# STM32F103xx_LQFP48.net
KiCad netlist of a schematic drawn in Altium Designer
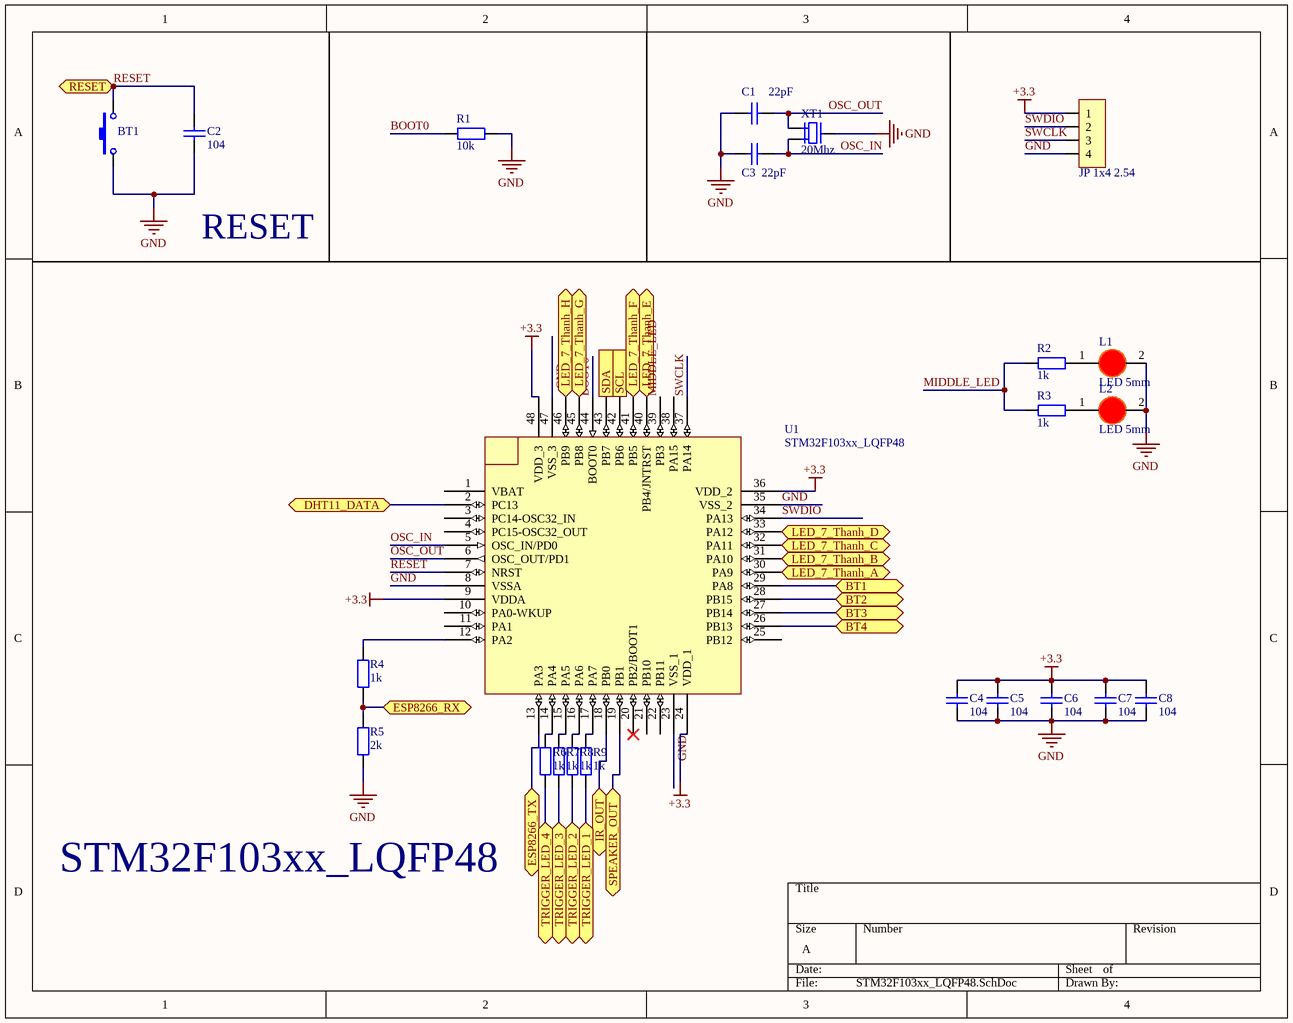
[diagram p0: STM32F103xx_LQFP48.SchDoc]

(export (version "E")
  (design (tool "Eeschema 10.0.6"))
  (components
    (comp (ref "BT1")
      (value "Nut Nhan 2 Chan SMD 3x6x2.5")
      (footprint "Nut Nhan 2 Chan SMD 3x6x2.5")
      (libsource (lib "Altium_Lib_by_KhueNguyenCreator") (part "Nut Nhan 2 Chan SMD 3x6x2.5"))
    )
    (comp (ref "C1")
      (value "22pF")
      (footprint "tu 0603")
      (description "Dán")
      (libsource (lib "Altium_Lib_by_KhueNguyenCreator") (part "Tu 0603 22pF 50V 10%"))
    )
    (comp (ref "C2")
      (value "104")
      (footprint "tu 0603")
      (description "Dán")
      (libsource (lib "Altium_Lib_by_KhueNguyenCreator") (part "Tu 0603 104 50V 10%"))
    )
    (comp (ref "C3")
      (value "22pF")
      (footprint "tu 0603")
      (description "Dán")
      (libsource (lib "Altium_Lib_by_KhueNguyenCreator") (part "Tu 0603 22pF 50V 10%"))
    )
    (comp (ref "C4")
      (value "104")
      (footprint "tu 0603")
      (description "Dán")
      (libsource (lib "Altium_Lib_by_KhueNguyenCreator") (part "Tu 0603 104 50V 10%"))
    )
    (comp (ref "C5")
      (value "104")
      (footprint "tu 0603")
      (description "Dán")
      (libsource (lib "Altium_Lib_by_KhueNguyenCreator") (part "Tu 0603 104 50V 10%"))
    )
    (comp (ref "C6")
      (value "104")
      (footprint "tu 0603")
      (description "Dán")
      (libsource (lib "Altium_Lib_by_KhueNguyenCreator") (part "Tu 0603 104 50V 10%"))
    )
    (comp (ref "C7")
      (value "104")
      (footprint "tu 0603")
      (description "Dán")
      (libsource (lib "Altium_Lib_by_KhueNguyenCreator") (part "Tu 0603 104 50V 10%"))
    )
    (comp (ref "C8")
      (value "104")
      (footprint "tu 0603")
      (description "Dán")
      (libsource (lib "Altium_Lib_by_KhueNguyenCreator") (part "Tu 0603 104 50V 10%"))
    )
    (comp (ref "JP1")
      (value "JP 1x4 2.54")
      (footprint "JP 1x4 DC")
      (description "Cắm")
      (libsource (lib "Altium_Lib_by_KhueNguyenCreator") (part "JP 1x4 2.54 Duc Cong"))
    )
    (comp (ref "L1")
      (value "LED 5mm")
      (footprint "LED-5MM-RED")
      (description "Cắm")
      (libsource (lib "Altium_Lib_by_KhueNguyenCreator") (part "LED 5mm Do"))
    )
    (comp (ref "L2")
      (value "LED 5mm")
      (footprint "LED-5MM-RED")
      (description "Cắm")
      (libsource (lib "Altium_Lib_by_KhueNguyenCreator") (part "LED 5mm Do"))
    )
    (comp (ref "R1")
      (value "10k")
      (footprint "tro smd 0603")
      (description "Dán")
      (libsource (lib "Altium_Lib_by_KhueNguyenCreator") (part "Tro 0603 1% 10k"))
    )
    (comp (ref "R2")
      (value "1k")
      (footprint "tro smd 0603")
      (description "Dán")
      (libsource (lib "Altium_Lib_by_KhueNguyenCreator") (part "Tro 0603 1% 1k"))
    )
    (comp (ref "R3")
      (value "1k")
      (footprint "tro smd 0603")
      (description "Dán")
      (libsource (lib "Altium_Lib_by_KhueNguyenCreator") (part "Tro 0603 1% 1k"))
    )
    (comp (ref "R4")
      (value "1k")
      (footprint "tro smd 0603")
      (description "Dán")
      (libsource (lib "Altium_Lib_by_KhueNguyenCreator") (part "Tro 0603 1% 1k"))
    )
    (comp (ref "R5")
      (value "2k")
      (footprint "tro smd 0603")
      (description "Dán")
      (libsource (lib "Altium_Lib_by_KhueNguyenCreator") (part "Tro 0603 5% 2k"))
    )
    (comp (ref "R6")
      (value "1k")
      (footprint "tro smd 0603")
      (description "Dán")
      (libsource (lib "Altium_Lib_by_KhueNguyenCreator") (part "Tro 0603 1% 1k"))
    )
    (comp (ref "R7")
      (value "1k")
      (footprint "tro smd 0603")
      (description "Dán")
      (libsource (lib "Altium_Lib_by_KhueNguyenCreator") (part "Tro 0603 1% 1k"))
    )
    (comp (ref "R8")
      (value "1k")
      (footprint "tro smd 0603")
      (description "Dán")
      (libsource (lib "Altium_Lib_by_KhueNguyenCreator") (part "Tro 0603 1% 1k"))
    )
    (comp (ref "R9")
      (value "1k")
      (footprint "tro smd 0603")
      (description "Dán")
      (libsource (lib "Altium_Lib_by_KhueNguyenCreator") (part "Tro 0603 1% 1k"))
    )
    (comp (ref "U1")
      (value "STM32F103xx_LQFP48")
      (footprint "STM32_LQPF48")
      (fields (field (name "PUBLISHER") "Altium Limited"))
      (libsource (lib "Altium_Lib_by_KhueNguyenCreator") (part "STM32F103xx_LQFP48"))
    )
    (comp (ref "XT1")
      (value "20Mhz")
      (footprint "Thach Anh 3 Chan SMD")
      (description "Crystal For all Crystal 2pin.")
      (libsource (lib "Altium_Lib_by_KhueNguyenCreator") (part "Thach anh 3 Chan SMD"))
    )
  )
  (nets
    (net (code "1") (name "+3.3") (class "Default")
      (node (ref "C4") (pin "1") (pinfunction "1_1") (pintype "passive"))
      (node (ref "C5") (pin "1") (pinfunction "1_1") (pintype "passive"))
      (node (ref "C6") (pin "1") (pinfunction "1_1") (pintype "passive"))
      (node (ref "C7") (pin "1") (pinfunction "1_1") (pintype "passive"))
      (node (ref "C8") (pin "1") (pinfunction "1_1") (pintype "passive"))
      (node (ref "JP1") (pin "1") (pinfunction "1_1") (pintype "passive"))
      (node (ref "U1") (pin "24") (pinfunction "VDD_1_24") (pintype "power_in"))
      (node (ref "U1") (pin "36") (pinfunction "VDD_2_36") (pintype "power_in"))
      (node (ref "U1") (pin "48") (pinfunction "VDD_3_48") (pintype "power_in"))
      (node (ref "U1") (pin "9") (pinfunction "VDDA_9") (pintype "power_in"))
    )
    (net (code "2") (name "/BOOT0") (class "Default")
      (node (ref "R1") (pin "1") (pinfunction "1_1") (pintype "passive"))
      (node (ref "U1") (pin "44") (pinfunction "BOOT0_44") (pintype "input"))
    )
    (net (code "3") (name "/BT1") (class "Default")
      (node (ref "U1") (pin "29") (pinfunction "PA8_29") (pintype "bidirectional"))
    )
    (net (code "4") (name "/BT2") (class "Default")
      (node (ref "U1") (pin "28") (pinfunction "PB15_28") (pintype "bidirectional"))
    )
    (net (code "5") (name "/BT3") (class "Default")
      (node (ref "U1") (pin "27") (pinfunction "PB14_27") (pintype "bidirectional"))
    )
    (net (code "6") (name "/BT4") (class "Default")
      (node (ref "U1") (pin "26") (pinfunction "PB13_26") (pintype "bidirectional"))
    )
    (net (code "7") (name "/DHT11_DATA") (class "Default")
      (node (ref "U1") (pin "2") (pinfunction "PC13_2") (pintype "bidirectional"))
    )
    (net (code "8") (name "/ESP8266_RX") (class "Default")
      (node (ref "R4") (pin "1") (pinfunction "1_1") (pintype "passive"))
      (node (ref "R5") (pin "2") (pinfunction "2_2") (pintype "passive"))
    )
    (net (code "9") (name "/ESP8266_TX") (class "Default")
      (node (ref "U1") (pin "13") (pinfunction "PA3_13") (pintype "bidirectional"))
    )
    (net (code "10") (name "/IR_OUT") (class "Default")
      (node (ref "U1") (pin "18") (pinfunction "PB0_18") (pintype "bidirectional"))
    )
    (net (code "11") (name "/LED_7_Thanh_A") (class "Default")
      (node (ref "U1") (pin "30") (pinfunction "PA9_30") (pintype "bidirectional"))
    )
    (net (code "12") (name "/LED_7_Thanh_B") (class "Default")
      (node (ref "U1") (pin "31") (pinfunction "PA10_31") (pintype "bidirectional"))
    )
    (net (code "13") (name "/LED_7_Thanh_C") (class "Default")
      (node (ref "U1") (pin "32") (pinfunction "PA11_32") (pintype "bidirectional"))
    )
    (net (code "14") (name "/LED_7_Thanh_D") (class "Default")
      (node (ref "U1") (pin "33") (pinfunction "PA12_33") (pintype "bidirectional"))
    )
    (net (code "15") (name "/LED_7_Thanh_E") (class "Default")
      (node (ref "U1") (pin "40") (pinfunction "PB4/JNTRST_40") (pintype "bidirectional"))
    )
    (net (code "16") (name "/LED_7_Thanh_F") (class "Default")
      (node (ref "U1") (pin "41") (pinfunction "PB5_41") (pintype "bidirectional"))
    )
    (net (code "17") (name "/LED_7_Thanh_G") (class "Default")
      (node (ref "U1") (pin "45") (pinfunction "PB8_45") (pintype "bidirectional"))
    )
    (net (code "18") (name "/LED_7_Thanh_H") (class "Default")
      (node (ref "U1") (pin "46") (pinfunction "PB9_46") (pintype "bidirectional"))
    )
    (net (code "19") (name "/MIDDLE_LED") (class "Default")
      (node (ref "R2") (pin "1") (pinfunction "1_1") (pintype "passive"))
      (node (ref "R3") (pin "1") (pinfunction "1_1") (pintype "passive"))
      (node (ref "U1") (pin "39") (pinfunction "PB3_39") (pintype "bidirectional"))
    )
    (net (code "20") (name "/OSC_IN") (class "Default")
      (node (ref "C3") (pin "1") (pinfunction "1_1") (pintype "passive"))
      (node (ref "U1") (pin "5") (pinfunction "OSC_IN/PD0_5") (pintype "input"))
      (node (ref "XT1") (pin "3") (pinfunction "3_3") (pintype "passive"))
    )
    (net (code "21") (name "/OSC_OUT") (class "Default")
      (node (ref "C1") (pin "1") (pinfunction "1_1") (pintype "passive"))
      (node (ref "U1") (pin "6") (pinfunction "OSC_OUT/PD1_6") (pintype "output"))
      (node (ref "XT1") (pin "1") (pinfunction "1_1") (pintype "passive"))
    )
    (net (code "22") (name "/RESET") (class "Default")
      (node (ref "BT1") (pin "2") (pinfunction "2_2") (pintype "passive"))
      (node (ref "C2") (pin "1") (pinfunction "1_1") (pintype "passive"))
      (node (ref "U1") (pin "7") (pinfunction "NRST_7") (pintype "bidirectional"))
    )
    (net (code "23") (name "/SCL") (class "Default")
      (node (ref "U1") (pin "42") (pinfunction "PB6_42") (pintype "bidirectional"))
    )
    (net (code "24") (name "/SDA") (class "Default")
      (node (ref "U1") (pin "43") (pinfunction "PB7_43") (pintype "bidirectional"))
    )
    (net (code "25") (name "/SPEAKER_OUT") (class "Default")
      (node (ref "U1") (pin "19") (pinfunction "PB1_19") (pintype "bidirectional"))
    )
    (net (code "26") (name "/SWCLK") (class "Default")
      (node (ref "JP1") (pin "3") (pinfunction "3_3") (pintype "passive"))
      (node (ref "U1") (pin "37") (pinfunction "PA14_37") (pintype "bidirectional"))
    )
    (net (code "27") (name "/SWDIO") (class "Default")
      (node (ref "JP1") (pin "2") (pinfunction "2_2") (pintype "passive"))
      (node (ref "U1") (pin "34") (pinfunction "PA13_34") (pintype "bidirectional"))
    )
    (net (code "28") (name "/TRIGGER_LED_1") (class "Default")
      (node (ref "R9") (pin "2") (pinfunction "2_2") (pintype "passive"))
    )
    (net (code "29") (name "/TRIGGER_LED_2") (class "Default")
      (node (ref "R8") (pin "2") (pinfunction "2_2") (pintype "passive"))
    )
    (net (code "30") (name "/TRIGGER_LED_3") (class "Default")
      (node (ref "R7") (pin "2") (pinfunction "2_2") (pintype "passive"))
    )
    (net (code "31") (name "/TRIGGER_LED_4") (class "Default")
      (node (ref "R6") (pin "2") (pinfunction "2_2") (pintype "passive"))
    )
    (net (code "32") (name "GND") (class "Default")
      (node (ref "BT1") (pin "1") (pinfunction "1_1") (pintype "passive"))
      (node (ref "C1") (pin "2") (pinfunction "2_2") (pintype "passive"))
      (node (ref "C2") (pin "2") (pinfunction "2_2") (pintype "passive"))
      (node (ref "C3") (pin "2") (pinfunction "2_2") (pintype "passive"))
      (node (ref "C4") (pin "2") (pinfunction "2_2") (pintype "passive"))
      (node (ref "C5") (pin "2") (pinfunction "2_2") (pintype "passive"))
      (node (ref "C6") (pin "2") (pinfunction "2_2") (pintype "passive"))
      (node (ref "C7") (pin "2") (pinfunction "2_2") (pintype "passive"))
      (node (ref "C8") (pin "2") (pinfunction "2_2") (pintype "passive"))
      (node (ref "JP1") (pin "4") (pinfunction "4_4") (pintype "passive"))
      (node (ref "L1") (pin "2") (pinfunction "K_2") (pintype "passive"))
      (node (ref "L2") (pin "2") (pinfunction "K_2") (pintype "passive"))
      (node (ref "R1") (pin "2") (pinfunction "2_2") (pintype "passive"))
      (node (ref "R5") (pin "1") (pinfunction "1_1") (pintype "passive"))
      (node (ref "U1") (pin "23") (pinfunction "VSS_1_23") (pintype "power_in"))
      (node (ref "U1") (pin "35") (pinfunction "VSS_2_35") (pintype "power_in"))
      (node (ref "U1") (pin "47") (pinfunction "VSS_3_47") (pintype "power_in"))
      (node (ref "U1") (pin "8") (pinfunction "VSSA_8") (pintype "power_in"))
      (node (ref "XT1") (pin "2") (pinfunction "2_2") (pintype "passive"))
    )
    (net (code "33") (name "Net-(L1-A)") (class "Default")
      (node (ref "L1") (pin "1") (pinfunction "A_1") (pintype "passive"))
      (node (ref "R2") (pin "2") (pinfunction "2_2") (pintype "passive"))
    )
    (net (code "34") (name "Net-(L2-A)") (class "Default")
      (node (ref "L2") (pin "1") (pinfunction "A_1") (pintype "passive"))
      (node (ref "R3") (pin "2") (pinfunction "2_2") (pintype "passive"))
    )
    (net (code "35") (name "Net-(U1-PA2)") (class "Default")
      (node (ref "R4") (pin "2") (pinfunction "2_2") (pintype "passive"))
      (node (ref "U1") (pin "12") (pinfunction "PA2_12") (pintype "bidirectional"))
    )
    (net (code "36") (name "Net-(U1-PA4)") (class "Default")
      (node (ref "R6") (pin "1") (pinfunction "1_1") (pintype "passive"))
      (node (ref "U1") (pin "14") (pinfunction "PA4_14") (pintype "bidirectional"))
    )
    (net (code "37") (name "Net-(U1-PA5)") (class "Default")
      (node (ref "R7") (pin "1") (pinfunction "1_1") (pintype "passive"))
      (node (ref "U1") (pin "15") (pinfunction "PA5_15") (pintype "bidirectional"))
    )
    (net (code "38") (name "Net-(U1-PA6)") (class "Default")
      (node (ref "R8") (pin "1") (pinfunction "1_1") (pintype "passive"))
      (node (ref "U1") (pin "16") (pinfunction "PA6_16") (pintype "bidirectional"))
    )
    (net (code "39") (name "Net-(U1-PA7)") (class "Default")
      (node (ref "R9") (pin "1") (pinfunction "1_1") (pintype "passive"))
      (node (ref "U1") (pin "17") (pinfunction "PA7_17") (pintype "bidirectional"))
    )
    (net (code "40") (name "unconnected-(U1-PA0-WKUP-Pad10)") (class "Default")
      (node (ref "U1") (pin "10") (pinfunction "PA0-WKUP_10") (pintype "bidirectional"))
    )
    (net (code "41") (name "unconnected-(U1-PA1-Pad11)") (class "Default")
      (node (ref "U1") (pin "11") (pinfunction "PA1_11") (pintype "bidirectional"))
    )
    (net (code "42") (name "unconnected-(U1-PA15-Pad38)") (class "Default")
      (node (ref "U1") (pin "38") (pinfunction "PA15_38") (pintype "bidirectional"))
    )
    (net (code "43") (name "unconnected-(U1-PB2{slash}BOOT1-Pad20)") (class "Default")
      (node (ref "U1") (pin "20") (pinfunction "PB2/BOOT1_20") (pintype "bidirectional+no_connect"))
    )
    (net (code "44") (name "unconnected-(U1-PB10-Pad21)") (class "Default")
      (node (ref "U1") (pin "21") (pinfunction "PB10_21") (pintype "bidirectional"))
    )
    (net (code "45") (name "unconnected-(U1-PB11-Pad22)") (class "Default")
      (node (ref "U1") (pin "22") (pinfunction "PB11_22") (pintype "bidirectional"))
    )
    (net (code "46") (name "unconnected-(U1-PB12-Pad25)") (class "Default")
      (node (ref "U1") (pin "25") (pinfunction "PB12_25") (pintype "bidirectional"))
    )
    (net (code "47") (name "unconnected-(U1-PC14-OSC32_IN-Pad3)") (class "Default")
      (node (ref "U1") (pin "3") (pinfunction "PC14-OSC32_IN_3") (pintype "bidirectional"))
    )
    (net (code "48") (name "unconnected-(U1-PC15-OSC32_OUT-Pad4)") (class "Default")
      (node (ref "U1") (pin "4") (pinfunction "PC15-OSC32_OUT_4") (pintype "bidirectional"))
    )
    (net (code "49") (name "unconnected-(U1-VBAT-Pad1)") (class "Default")
      (node (ref "U1") (pin "1") (pinfunction "VBAT_1") (pintype "power_in"))
    )
  )
)
